# leo_BMS_MCU.net
KiCad netlist of a schematic drawn in Altium Designer
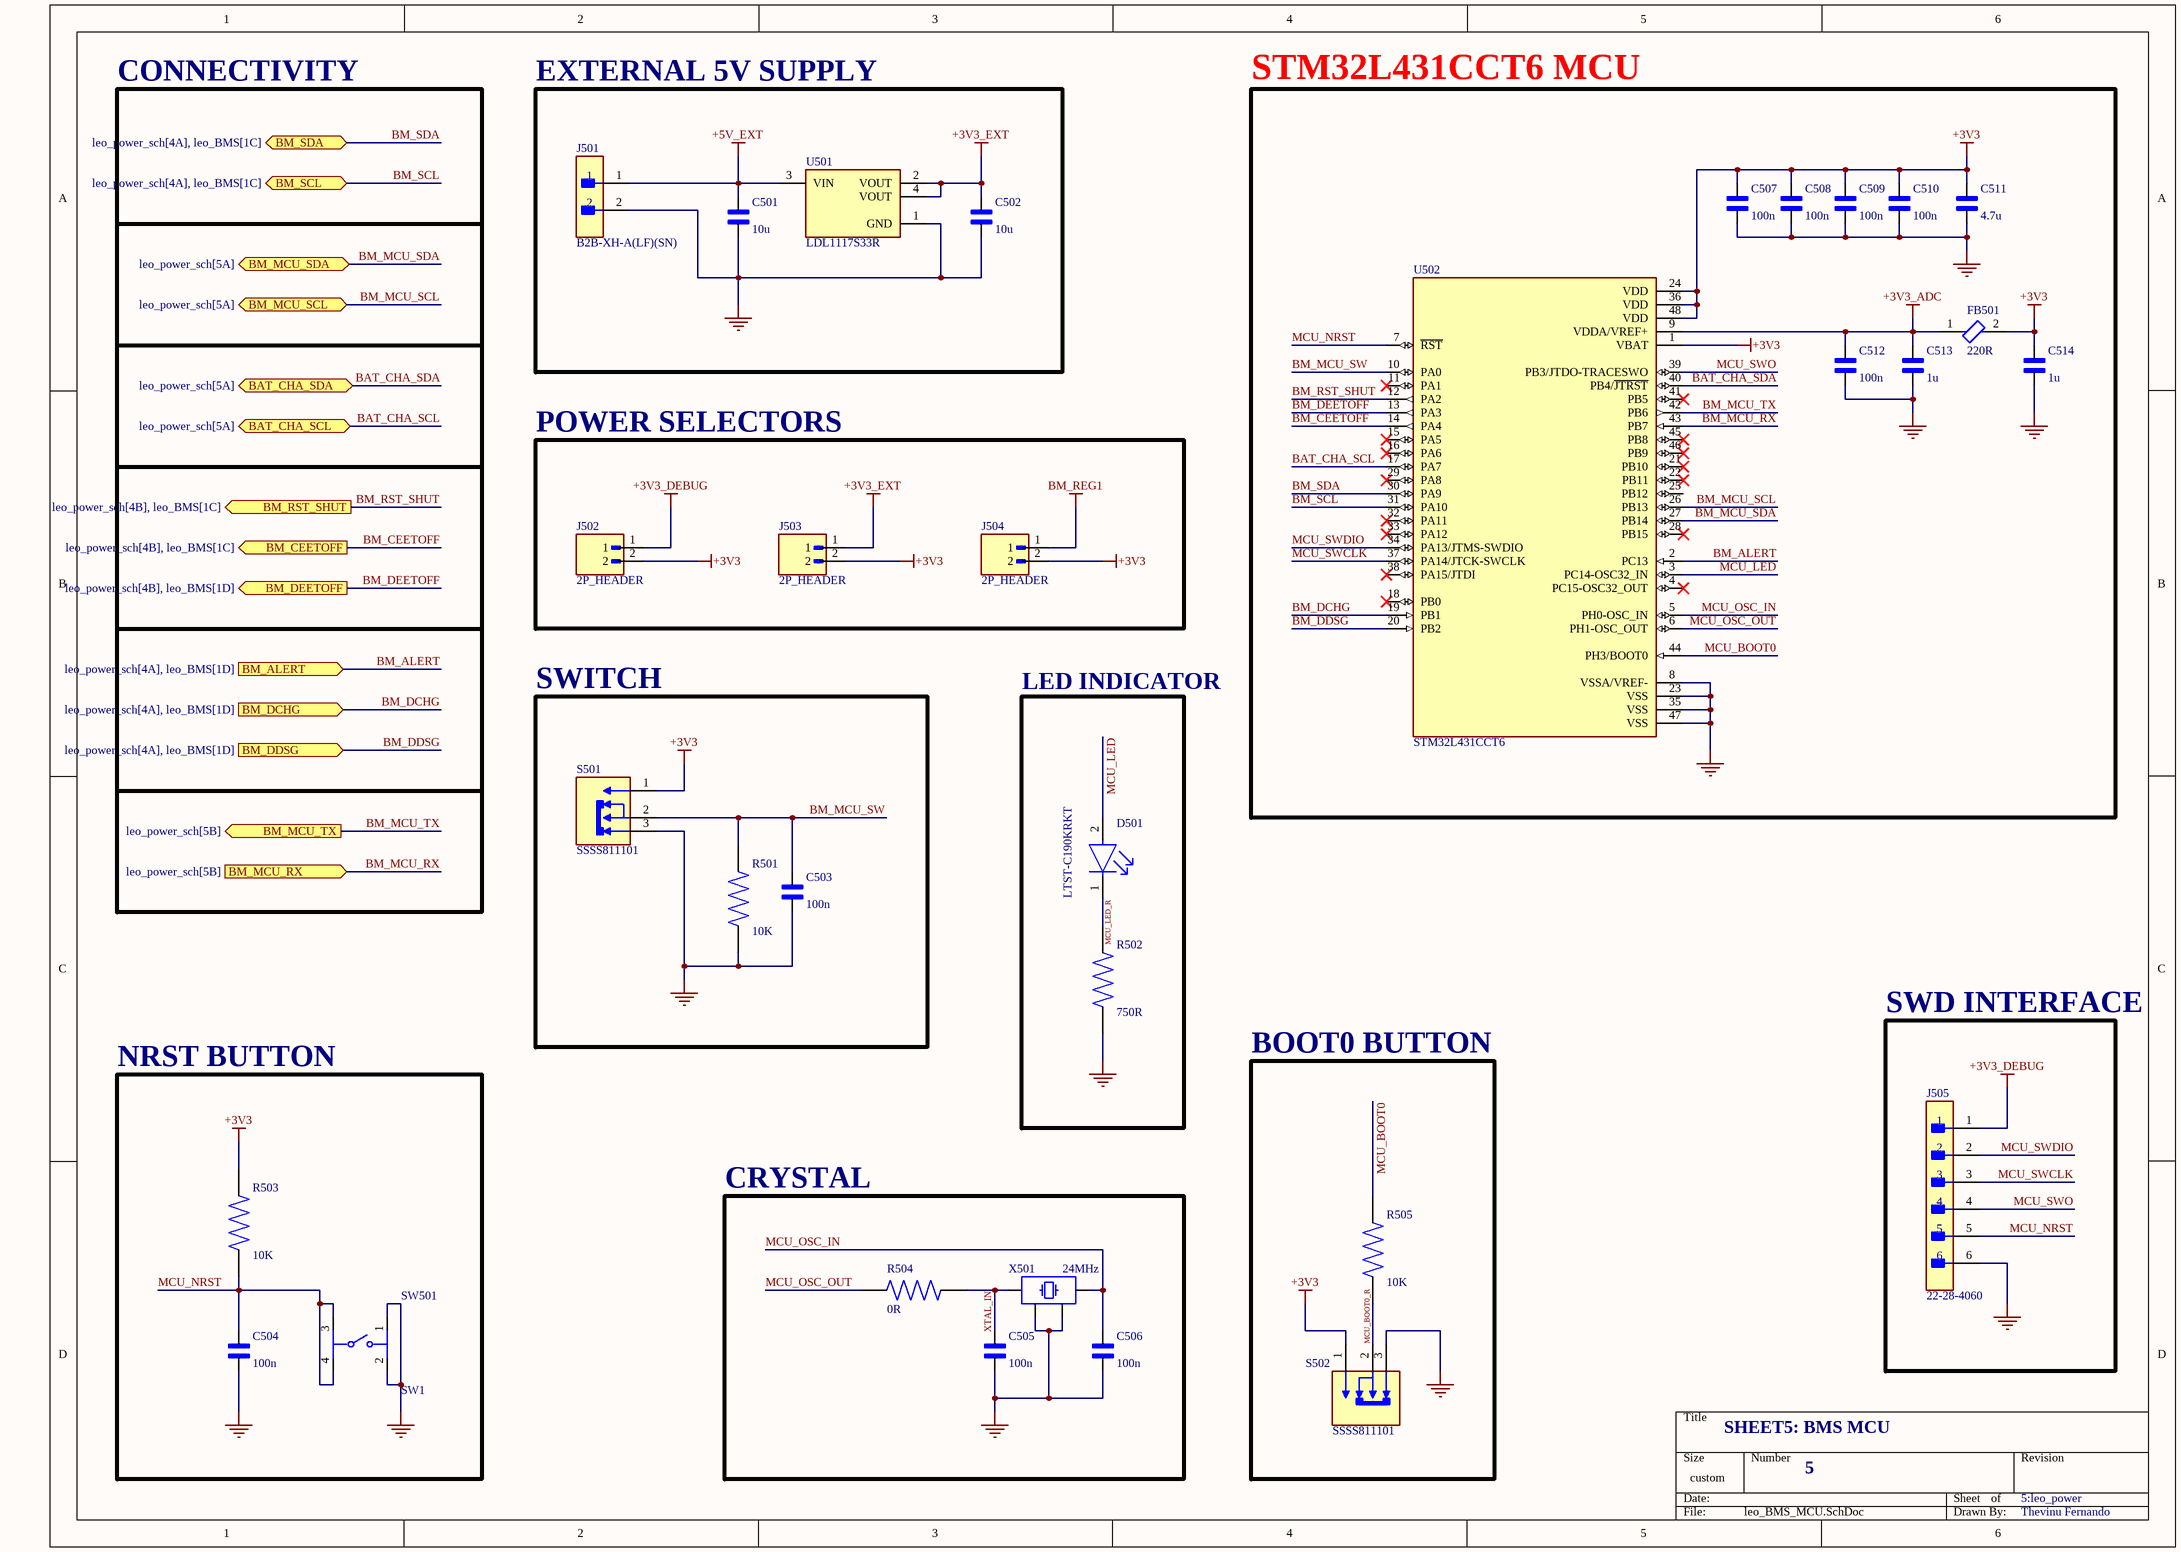
[diagram p0: leo_BMS_MCU.SchDoc]

(export (version "E")
  (design (tool "Eeschema 10.0.6"))
  (components
    (comp (ref "C501")
      (value "10u")
      (footprint "CAP_0805")
      (description "Ceramic Capacitor X7R 0805 (2012 Metric)")
      (fields (field (name "MF") "Samsung Electro-Mechanics") (field (name "MP") "CL21B106KOQNNNE"))
      (libsource (lib "leo_power_schlib") (part "CAP_0805"))
    )
    (comp (ref "C502")
      (value "10u")
      (footprint "CAP_0805")
      (description "Ceramic Capacitor X7R 0805 (2012 Metric)")
      (fields (field (name "MF") "Samsung Electro-Mechanics") (field (name "MP") "CL21B106KOQNNNE"))
      (libsource (lib "leo_power_schlib") (part "CAP_0805"))
    )
    (comp (ref "C503")
      (value "100n")
      (footprint "CAP_0402")
      (description "±10% 50V Ceramic Capacitor X7R 0402")
      (fields (field (name "MF") "Samsung") (field (name "MP") "CL05B104KO5NNNC"))
      (libsource (lib "leo_power_schlib") (part "CAP_0402"))
    )
    (comp (ref "C504")
      (value "100n")
      (footprint "CAP_0402")
      (description "±10% 50V Ceramic Capacitor X7R 0402")
      (fields (field (name "MF") "Samsung") (field (name "MP") "CL05B104KO5NNNC"))
      (libsource (lib "leo_power_schlib") (part "CAP_0402"))
    )
    (comp (ref "C505")
      (value "100n")
      (footprint "CAP_0402")
      (description "±10% 50V Ceramic Capacitor X7R 0402")
      (fields (field (name "MF") "Samsung") (field (name "MP") "CL05B104KO5NNNC"))
      (libsource (lib "leo_power_schlib") (part "CAP_0402"))
    )
    (comp (ref "C506")
      (value "100n")
      (footprint "CAP_0402")
      (description "±10% 50V Ceramic Capacitor X7R 0402")
      (fields (field (name "MF") "Samsung") (field (name "MP") "CL05B104KO5NNNC"))
      (libsource (lib "leo_power_schlib") (part "CAP_0402"))
    )
    (comp (ref "C507")
      (value "100n")
      (footprint "CAP_0402")
      (description "±10% 50V Ceramic Capacitor X7R 0402")
      (fields (field (name "MF") "Samsung") (field (name "MP") "CL05B104KO5NNNC"))
      (libsource (lib "leo_power_schlib") (part "CAP_0402"))
    )
    (comp (ref "C508")
      (value "100n")
      (footprint "CAP_0402")
      (description "±10% 50V Ceramic Capacitor X7R 0402")
      (fields (field (name "MF") "Samsung") (field (name "MP") "CL05B104KO5NNNC"))
      (libsource (lib "leo_power_schlib") (part "CAP_0402"))
    )
    (comp (ref "C509")
      (value "100n")
      (footprint "CAP_0402")
      (description "±10% 50V Ceramic Capacitor X7R 0402")
      (fields (field (name "MF") "Samsung") (field (name "MP") "CL05B104KO5NNNC"))
      (libsource (lib "leo_power_schlib") (part "CAP_0402"))
    )
    (comp (ref "C510")
      (value "100n")
      (footprint "CAP_0402")
      (description "±10% 50V Ceramic Capacitor X7R 0402")
      (fields (field (name "MF") "Samsung") (field (name "MP") "CL05B104KO5NNNC"))
      (libsource (lib "leo_power_schlib") (part "CAP_0402"))
    )
    (comp (ref "C511")
      (value "4.7u")
      (footprint "CAP_0603")
      (description "Â±10% 50V Ceramic Capacitor X7R 0603 (1608 Metric)")
      (fields (field (name "MF") "Samsung Electro-Mechanics") (field (name "MP") "CL10B104KB8NNNC"))
      (libsource (lib "leo_power_schlib") (part "CAP_0603"))
    )
    (comp (ref "C512")
      (value "100n")
      (footprint "CAP_0402")
      (description "±10% 50V Ceramic Capacitor X7R 0402")
      (fields (field (name "MF") "Samsung") (field (name "MP") "CL05B104KO5NNNC"))
      (libsource (lib "leo_power_schlib") (part "CAP_0402"))
    )
    (comp (ref "C513")
      (value "1u")
      (footprint "CAP_0603")
      (description "Â±10% 50V Ceramic Capacitor X7R 0603 (1608 Metric)")
      (fields (field (name "MF") "Samsung Electro-Mechanics") (field (name "MP") "CL10B104KB8NNNC"))
      (libsource (lib "leo_power_schlib") (part "CAP_0603"))
    )
    (comp (ref "C514")
      (value "1u")
      (footprint "CAP_0603")
      (description "Â±10% 50V Ceramic Capacitor X7R 0603 (1608 Metric)")
      (fields (field (name "MF") "Samsung Electro-Mechanics") (field (name "MP") "CL10B104KB8NNNC"))
      (libsource (lib "leo_power_schlib") (part "CAP_0603"))
    )
    (comp (ref "D501")
      (value "LTST-C190KRKT")
      (footprint "FP-LTST-C190KRKT-MFG")
      (description "LED RED CLEAR CHIP SMD")
      (libsource (lib "leo_power_schlib") (part "RED_LED"))
    )
    (comp (ref "FB501")
      (value "220R")
      (footprint "FP-MPZ1608-0_8-IPC_B")
      (description "Power line Ferrite Bead 220Ω @ 100MHz 2.2A DCR 0.05Ω SMD 0603")
      (fields (field (name "TOLERANCE") "25%"))
      (libsource (lib "leo_power_schlib") (part "Ferrite_Bead_220R_0603"))
    )
    (comp (ref "J501")
      (value "B2B-XH-A(LF)(SN)")
      (footprint "FP-B2B-XH-A_LF_SN-MFG")
      (description "CONN HEADER VERT 2POS 2.5MM")
      (libsource (lib "leo_power_schlib") (part "B2B-XH-A(LF)(SN)"))
    )
    (comp (ref "J502")
      (value "2P_HEADER")
      (footprint "HARWIN_M20-9990246 2P Header")
      (description "2.54mm (0.1) Pitch SIL Vertical Throughboard Pin Header, 6.1mm mating pin height, tin, 2 contacts")
      (fields (field (name "MF") "Harwin") (field (name "MP") "M20-9990246"))
      (libsource (lib "leo_power_schlib") (part "2P_HEADER"))
    )
    (comp (ref "J503")
      (value "2P_HEADER")
      (footprint "HARWIN_M20-9990246 2P Header")
      (description "2.54mm (0.1) Pitch SIL Vertical Throughboard Pin Header, 6.1mm mating pin height, tin, 2 contacts")
      (fields (field (name "MF") "Harwin") (field (name "MP") "M20-9990246"))
      (libsource (lib "leo_power_schlib") (part "2P_HEADER"))
    )
    (comp (ref "J504")
      (value "2P_HEADER")
      (footprint "HARWIN_M20-9990246 2P Header")
      (description "2.54mm (0.1) Pitch SIL Vertical Throughboard Pin Header, 6.1mm mating pin height, tin, 2 contacts")
      (fields (field (name "MF") "Harwin") (field (name "MP") "M20-9990246"))
      (libsource (lib "leo_power_schlib") (part "2P_HEADER"))
    )
    (comp (ref "J505")
      (value "22-28-4060")
      (footprint "FP-22-28-4060-MFG")
      (description "CONN HEADER VERT 6POS 2.54MM")
      (libsource (lib "leo_power_schlib") (part "6P_M_HEADER"))
    )
    (comp (ref "R501")
      (value "10K")
      (footprint "RES_0402")
      (description "Chip Resistor 0402 (1005 Metric) Automotive AEC-Q200 Thick Film")
      (fields (field (name "MF") "Panasonic") (field (name "MP") "ERJ-2RKF1002X"))
      (libsource (lib "leo_power_schlib") (part "RES_0402"))
    )
    (comp (ref "R502")
      (value "750R")
      (footprint "RES_0603")
      (description "Â±1% 0.1W, 1/10W Chip Resistor 0603 (1608 Metric) Moisture Resistant Thick Film")
      (fields (field (name "MF") "Yageo") (field (name "MP") "RC0603FR-0791KL"))
      (libsource (lib "leo_power_schlib") (part "RES_0603"))
    )
    (comp (ref "R503")
      (value "10K")
      (footprint "RES_0402")
      (description "Chip Resistor 0402 (1005 Metric) Automotive AEC-Q200 Thick Film")
      (fields (field (name "MF") "Panasonic") (field (name "MP") "ERJ-2RKF1002X"))
      (libsource (lib "leo_power_schlib") (part "RES_0402"))
    )
    (comp (ref "R504")
      (value "0R")
      (footprint "RES_0402")
      (description "Chip Resistor 0402 (1005 Metric) Automotive AEC-Q200 Thick Film")
      (fields (field (name "MF") "Panasonic") (field (name "MP") "ERJ-2RKF1002X"))
      (libsource (lib "leo_power_schlib") (part "RES_0402"))
    )
    (comp (ref "R505")
      (value "10K")
      (footprint "RES_0402")
      (description "Chip Resistor 0402 (1005 Metric) Automotive AEC-Q200 Thick Film")
      (fields (field (name "MF") "Panasonic") (field (name "MP") "ERJ-2RKF1002X"))
      (libsource (lib "leo_power_schlib") (part "RES_0402"))
    )
    (comp (ref "S501")
      (value "SSSS811101")
      (footprint "SW_SSSS811101")
      (description "Switch Slide SP Side Slide 0.3A 5VDC 10000Cycles Gull Wing SMD T/R")
      (fields (field (name "MF") "ALPS"))
      (libsource (lib "") (part "SSSS811101_1"))
    )
    (comp (ref "S502")
      (value "SSSS811101")
      (footprint "SW_SSSS811101")
      (description "Switch Slide SP Side Slide 0.3A 5VDC 10000Cycles Gull Wing SMD T/R")
      (fields (field (name "MF") "ALPS"))
      (libsource (lib "leo_power_schlib") (part "SSSS811101"))
    )
    (comp (ref "SW501")
      (value "SW1")
      (footprint "FP-PTS645SM43SMTR92LFS-MFG")
      (description "Tactile Switch SPST 160gf 4.3mm Gull Wing 6mm x 6mm Surface Mount")
      (libsource (lib "leo_power_schlib") (part "PTS645SM43SMTR92LFS"))
    )
    (comp (ref "U501")
      (value "LDL1117S33R")
      (footprint "FP-SOT223-0046067-IPC_A")
      (description "IC REG LINEAR 3.3V 1.2A SOT223")
      (fields
        (field (name "OCTOPART") "https://octopart.com/ldl1117s33r-stmicroelectronics-81876163")
        (field (name "MANUFACTURER") "STMicroelectronics")
      )
      (libsource (lib "leo_power_schlib") (part "LDO_LDL1117S33R"))
    )
    (comp (ref "U502")
      (value "STM32L431CCT6")
      (footprint "QFP50P900X900X160-48N")
      (fields (field (name "MF") "STMicroelectronics"))
      (libsource (lib "leo_power_schlib") (part "STM32L431CCT6"))
    )
    (comp (ref "X501")
      (value "24MHz")
      (footprint "XTAL_3225")
      (description "Crystal SMD 24MHz 10PPM 7pF 3225")
      (fields
        (field (name "MANUFACTURER") "Epson")
        (field (name "MANUFACTURER PART NUMBER") "TSX-3225 24.0000MF15X-AC")
      )
      (libsource (lib "leo_power_schlib") (part "TSX-3225_24.0000MF15X-AC"))
    )
  )
  (nets
    (net (code "1") (name "+3V3") (class "Default")
      (node (ref "C507") (pin "2") (pinfunction "2_2") (pintype "passive"))
      (node (ref "C508") (pin "2") (pinfunction "2_2") (pintype "passive"))
      (node (ref "C509") (pin "2") (pinfunction "2_2") (pintype "passive"))
      (node (ref "C510") (pin "2") (pinfunction "2_2") (pintype "passive"))
      (node (ref "C511") (pin "2") (pinfunction "2_2") (pintype "passive"))
      (node (ref "C514") (pin "2") (pinfunction "2_2") (pintype "passive"))
      (node (ref "FB501") (pin "2") (pinfunction "2_2") (pintype "passive"))
      (node (ref "J502") (pin "2") (pinfunction "2_2") (pintype "passive"))
      (node (ref "J503") (pin "2") (pinfunction "2_2") (pintype "passive"))
      (node (ref "J504") (pin "2") (pinfunction "2_2") (pintype "passive"))
      (node (ref "R503") (pin "2") (pinfunction "2_2") (pintype "passive"))
      (node (ref "S501") (pin "1") (pinfunction "1_1") (pintype "passive"))
      (node (ref "S502") (pin "1") (pinfunction "1_1") (pintype "passive"))
      (node (ref "U502") (pin "1") (pinfunction "VBAT_1") (pintype "power_in"))
      (node (ref "U502") (pin "24") (pinfunction "VDD_24") (pintype "power_in"))
      (node (ref "U502") (pin "36") (pinfunction "VDD_36") (pintype "power_in"))
      (node (ref "U502") (pin "48") (pinfunction "VDD_48") (pintype "power_in"))
    )
    (net (code "2") (name "+3V3_ADC") (class "Default")
      (node (ref "C512") (pin "2") (pinfunction "2_2") (pintype "passive"))
      (node (ref "C513") (pin "2") (pinfunction "2_2") (pintype "passive"))
      (node (ref "FB501") (pin "1") (pinfunction "1_1") (pintype "passive"))
      (node (ref "U502") (pin "9") (pinfunction "VDDA/VREF+_9") (pintype "power_in"))
    )
    (net (code "3") (name "+3V3_DEBUG") (class "Default")
      (node (ref "J502") (pin "1") (pinfunction "1_1") (pintype "passive"))
      (node (ref "J505") (pin "1") (pinfunction "1_1") (pintype "passive"))
    )
    (net (code "4") (name "+3V3_EXT") (class "Default")
      (node (ref "C502") (pin "1") (pinfunction "1_1") (pintype "passive"))
      (node (ref "J503") (pin "1") (pinfunction "1_1") (pintype "passive"))
      (node (ref "U501") (pin "2") (pinfunction "VOUT_2") (pintype "power_in"))
      (node (ref "U501") (pin "4") (pinfunction "VOUT_4") (pintype "power_in"))
    )
    (net (code "5") (name "+5V_EXT") (class "Default")
      (node (ref "C501") (pin "1") (pinfunction "1_1") (pintype "passive"))
      (node (ref "J501") (pin "1") (pinfunction "1_1") (pintype "passive"))
      (node (ref "U501") (pin "3") (pinfunction "VIN_3") (pintype "power_in"))
    )
    (net (code "6") (name "/BAT_CHA_SCL") (class "Default")
      (node (ref "U502") (pin "17") (pinfunction "PA7_17") (pintype "bidirectional"))
    )
    (net (code "7") (name "/BAT_CHA_SDA") (class "Default")
      (node (ref "U502") (pin "40") (pinfunction "PB4/~{JTRST}_40") (pintype "bidirectional"))
    )
    (net (code "8") (name "/BM_ALERT") (class "Default")
      (node (ref "U502") (pin "2") (pinfunction "PC13_2") (pintype "input"))
    )
    (net (code "9") (name "/BM_CEETOFF") (class "Default")
      (node (ref "U502") (pin "14") (pinfunction "PA4_14") (pintype "output"))
    )
    (net (code "10") (name "/BM_DCHG") (class "Default")
      (node (ref "U502") (pin "19") (pinfunction "PB1_19") (pintype "input"))
    )
    (net (code "11") (name "/BM_DDSG") (class "Default")
      (node (ref "U502") (pin "20") (pinfunction "PB2_20") (pintype "input"))
    )
    (net (code "12") (name "/BM_DEETOFF") (class "Default")
      (node (ref "U502") (pin "13") (pinfunction "PA3_13") (pintype "output"))
    )
    (net (code "13") (name "/BM_MCU_RX") (class "Default")
      (node (ref "U502") (pin "43") (pinfunction "PB7_43") (pintype "input"))
    )
    (net (code "14") (name "/BM_MCU_SCL") (class "Default")
      (node (ref "U502") (pin "26") (pinfunction "PB13_26") (pintype "bidirectional"))
    )
    (net (code "15") (name "/BM_MCU_SDA") (class "Default")
      (node (ref "U502") (pin "27") (pinfunction "PB14_27") (pintype "bidirectional"))
    )
    (net (code "16") (name "/BM_MCU_SW") (class "Default")
      (node (ref "C503") (pin "2") (pinfunction "2_2") (pintype "passive"))
      (node (ref "R501") (pin "2") (pinfunction "2_2") (pintype "passive"))
      (node (ref "S501") (pin "2") (pinfunction "2_2") (pintype "passive"))
      (node (ref "U502") (pin "10") (pinfunction "PA0_10") (pintype "bidirectional"))
    )
    (net (code "17") (name "/BM_MCU_TX") (class "Default")
      (node (ref "U502") (pin "42") (pinfunction "PB6_42") (pintype "output"))
    )
    (net (code "18") (name "/BM_RST_SHUT") (class "Default")
      (node (ref "U502") (pin "12") (pinfunction "PA2_12") (pintype "output"))
    )
    (net (code "19") (name "/BM_SCL") (class "Default")
      (node (ref "U502") (pin "31") (pinfunction "PA10_31") (pintype "bidirectional"))
    )
    (net (code "20") (name "/BM_SDA") (class "Default")
      (node (ref "U502") (pin "30") (pinfunction "PA9_30") (pintype "bidirectional"))
    )
    (net (code "21") (name "/MCU_BOOT0") (class "Default")
      (node (ref "R505") (pin "2") (pinfunction "2_2") (pintype "passive"))
      (node (ref "U502") (pin "44") (pinfunction "PH3/BOOT0_44") (pintype "input"))
    )
    (net (code "22") (name "/MCU_BOOT0_R") (class "Default")
      (node (ref "R505") (pin "1") (pinfunction "1_1") (pintype "passive"))
      (node (ref "S502") (pin "2") (pinfunction "2_2") (pintype "passive"))
    )
    (net (code "23") (name "/MCU_LED") (class "Default")
      (node (ref "D501") (pin "2") (pinfunction "A_2") (pintype "passive"))
      (node (ref "U502") (pin "3") (pinfunction "PC14-OSC32_IN_3") (pintype "bidirectional"))
    )
    (net (code "24") (name "/MCU_LED_R") (class "Default")
      (node (ref "D501") (pin "1") (pinfunction "C_1") (pintype "passive"))
      (node (ref "R502") (pin "2") (pinfunction "2_2") (pintype "passive"))
    )
    (net (code "25") (name "/MCU_NRST") (class "Default")
      (node (ref "C504") (pin "2") (pinfunction "2_2") (pintype "passive"))
      (node (ref "J505") (pin "5") (pinfunction "5_5") (pintype "passive"))
      (node (ref "R503") (pin "1") (pinfunction "1_1") (pintype "passive"))
      (node (ref "SW501") (pin "3") (pinfunction "3_3") (pintype "passive"))
      (node (ref "SW501") (pin "4") (pinfunction "4_4") (pintype "passive"))
      (node (ref "U502") (pin "7") (pinfunction "~{RST}_7") (pintype "bidirectional"))
    )
    (net (code "26") (name "/MCU_OSC_IN") (class "Default")
      (node (ref "C506") (pin "2") (pinfunction "2_2") (pintype "passive"))
      (node (ref "U502") (pin "5") (pinfunction "PH0-OSC_IN_5") (pintype "bidirectional"))
      (node (ref "X501") (pin "3") (pinfunction "3_3") (pintype "passive"))
    )
    (net (code "27") (name "/MCU_OSC_OUT") (class "Default")
      (node (ref "R504") (pin "2") (pinfunction "2_2") (pintype "passive"))
      (node (ref "U502") (pin "6") (pinfunction "PH1-OSC_OUT_6") (pintype "bidirectional"))
    )
    (net (code "28") (name "/MCU_SWCLK") (class "Default")
      (node (ref "J505") (pin "3") (pinfunction "3_3") (pintype "passive"))
      (node (ref "U502") (pin "37") (pinfunction "PA14/JTCK-SWCLK_37") (pintype "bidirectional"))
    )
    (net (code "29") (name "/MCU_SWDIO") (class "Default")
      (node (ref "J505") (pin "2") (pinfunction "2_2") (pintype "passive"))
      (node (ref "U502") (pin "34") (pinfunction "PA13/JTMS-SWDIO_34") (pintype "bidirectional"))
    )
    (net (code "30") (name "/MCU_SWO") (class "Default")
      (node (ref "J505") (pin "4") (pinfunction "4_4") (pintype "passive"))
      (node (ref "U502") (pin "39") (pinfunction "PB3/JTDO-TRACESWO_39") (pintype "bidirectional"))
    )
    (net (code "31") (name "/XTAL_IN") (class "Default")
      (node (ref "C505") (pin "2") (pinfunction "2_2") (pintype "passive"))
      (node (ref "R504") (pin "1") (pinfunction "1_1") (pintype "passive"))
      (node (ref "X501") (pin "1") (pinfunction "1_1") (pintype "passive"))
    )
    (net (code "32") (name "BM_REG1") (class "Default")
      (node (ref "J504") (pin "1") (pinfunction "1_1") (pintype "passive"))
    )
    (net (code "33") (name "GND") (class "Default")
      (node (ref "C501") (pin "2") (pinfunction "2_2") (pintype "passive"))
      (node (ref "C502") (pin "2") (pinfunction "2_2") (pintype "passive"))
      (node (ref "C503") (pin "1") (pinfunction "1_1") (pintype "passive"))
      (node (ref "C504") (pin "1") (pinfunction "1_1") (pintype "passive"))
      (node (ref "C505") (pin "1") (pinfunction "1_1") (pintype "passive"))
      (node (ref "C506") (pin "1") (pinfunction "1_1") (pintype "passive"))
      (node (ref "C507") (pin "1") (pinfunction "1_1") (pintype "passive"))
      (node (ref "C508") (pin "1") (pinfunction "1_1") (pintype "passive"))
      (node (ref "C509") (pin "1") (pinfunction "1_1") (pintype "passive"))
      (node (ref "C510") (pin "1") (pinfunction "1_1") (pintype "passive"))
      (node (ref "C511") (pin "1") (pinfunction "1_1") (pintype "passive"))
      (node (ref "C512") (pin "1") (pinfunction "1_1") (pintype "passive"))
      (node (ref "C513") (pin "1") (pinfunction "1_1") (pintype "passive"))
      (node (ref "C514") (pin "1") (pinfunction "1_1") (pintype "passive"))
      (node (ref "J501") (pin "2") (pinfunction "2_2") (pintype "passive"))
      (node (ref "J505") (pin "6") (pinfunction "6_6") (pintype "passive"))
      (node (ref "R501") (pin "1") (pinfunction "1_1") (pintype "passive"))
      (node (ref "R502") (pin "1") (pinfunction "1_1") (pintype "passive"))
      (node (ref "S501") (pin "3") (pinfunction "3_3") (pintype "passive"))
      (node (ref "S502") (pin "3") (pinfunction "3_3") (pintype "passive"))
      (node (ref "SW501") (pin "1") (pinfunction "1_1") (pintype "passive"))
      (node (ref "SW501") (pin "2") (pinfunction "2_2") (pintype "passive"))
      (node (ref "U501") (pin "1") (pinfunction "GND_1") (pintype "power_in"))
      (node (ref "U502") (pin "23") (pinfunction "VSS_23") (pintype "power_in"))
      (node (ref "U502") (pin "35") (pinfunction "VSS_35") (pintype "power_in"))
      (node (ref "U502") (pin "47") (pinfunction "VSS_47") (pintype "power_in"))
      (node (ref "U502") (pin "8") (pinfunction "VSSA/VREF-_8") (pintype "power_in"))
      (node (ref "X501") (pin "2") (pinfunction "2_2") (pintype "passive"))
      (node (ref "X501") (pin "4") (pinfunction "4_4") (pintype "passive"))
    )
    (net (code "34") (name "unconnected-(U502-PA1-Pad11)") (class "Default")
      (node (ref "U502") (pin "11") (pinfunction "PA1_11") (pintype "bidirectional+no_connect"))
    )
    (net (code "35") (name "unconnected-(U502-PA5-Pad15)") (class "Default")
      (node (ref "U502") (pin "15") (pinfunction "PA5_15") (pintype "bidirectional+no_connect"))
    )
    (net (code "36") (name "unconnected-(U502-PA6-Pad16)") (class "Default")
      (node (ref "U502") (pin "16") (pinfunction "PA6_16") (pintype "bidirectional+no_connect"))
    )
    (net (code "37") (name "unconnected-(U502-PA8-Pad29)") (class "Default")
      (node (ref "U502") (pin "29") (pinfunction "PA8_29") (pintype "bidirectional+no_connect"))
    )
    (net (code "38") (name "unconnected-(U502-PA11-Pad32)") (class "Default")
      (node (ref "U502") (pin "32") (pinfunction "PA11_32") (pintype "bidirectional+no_connect"))
    )
    (net (code "39") (name "unconnected-(U502-PA12-Pad33)") (class "Default")
      (node (ref "U502") (pin "33") (pinfunction "PA12_33") (pintype "bidirectional+no_connect"))
    )
    (net (code "40") (name "unconnected-(U502-PA15{slash}JTDI-Pad38)") (class "Default")
      (node (ref "U502") (pin "38") (pinfunction "PA15/JTDI_38") (pintype "bidirectional+no_connect"))
    )
    (net (code "41") (name "unconnected-(U502-PB0-Pad18)") (class "Default")
      (node (ref "U502") (pin "18") (pinfunction "PB0_18") (pintype "bidirectional+no_connect"))
    )
    (net (code "42") (name "unconnected-(U502-PB5-Pad41)") (class "Default")
      (node (ref "U502") (pin "41") (pinfunction "PB5_41") (pintype "bidirectional+no_connect"))
    )
    (net (code "43") (name "unconnected-(U502-PB8-Pad45)") (class "Default")
      (node (ref "U502") (pin "45") (pinfunction "PB8_45") (pintype "bidirectional+no_connect"))
    )
    (net (code "44") (name "unconnected-(U502-PB9-Pad46)") (class "Default")
      (node (ref "U502") (pin "46") (pinfunction "PB9_46") (pintype "bidirectional+no_connect"))
    )
    (net (code "45") (name "unconnected-(U502-PB10-Pad21)") (class "Default")
      (node (ref "U502") (pin "21") (pinfunction "PB10_21") (pintype "bidirectional+no_connect"))
    )
    (net (code "46") (name "unconnected-(U502-PB11-Pad22)") (class "Default")
      (node (ref "U502") (pin "22") (pinfunction "PB11_22") (pintype "bidirectional+no_connect"))
    )
    (net (code "47") (name "unconnected-(U502-PB12-Pad25)") (class "Default")
      (node (ref "U502") (pin "25") (pinfunction "PB12_25") (pintype "bidirectional"))
    )
    (net (code "48") (name "unconnected-(U502-PB15-Pad28)") (class "Default")
      (node (ref "U502") (pin "28") (pinfunction "PB15_28") (pintype "bidirectional+no_connect"))
    )
    (net (code "49") (name "unconnected-(U502-PC15-OSC32_OUT-Pad4)") (class "Default")
      (node (ref "U502") (pin "4") (pinfunction "PC15-OSC32_OUT_4") (pintype "bidirectional+no_connect"))
    )
  )
)
